# charger.net
KiCad netlist of a schematic drawn in EAGLE
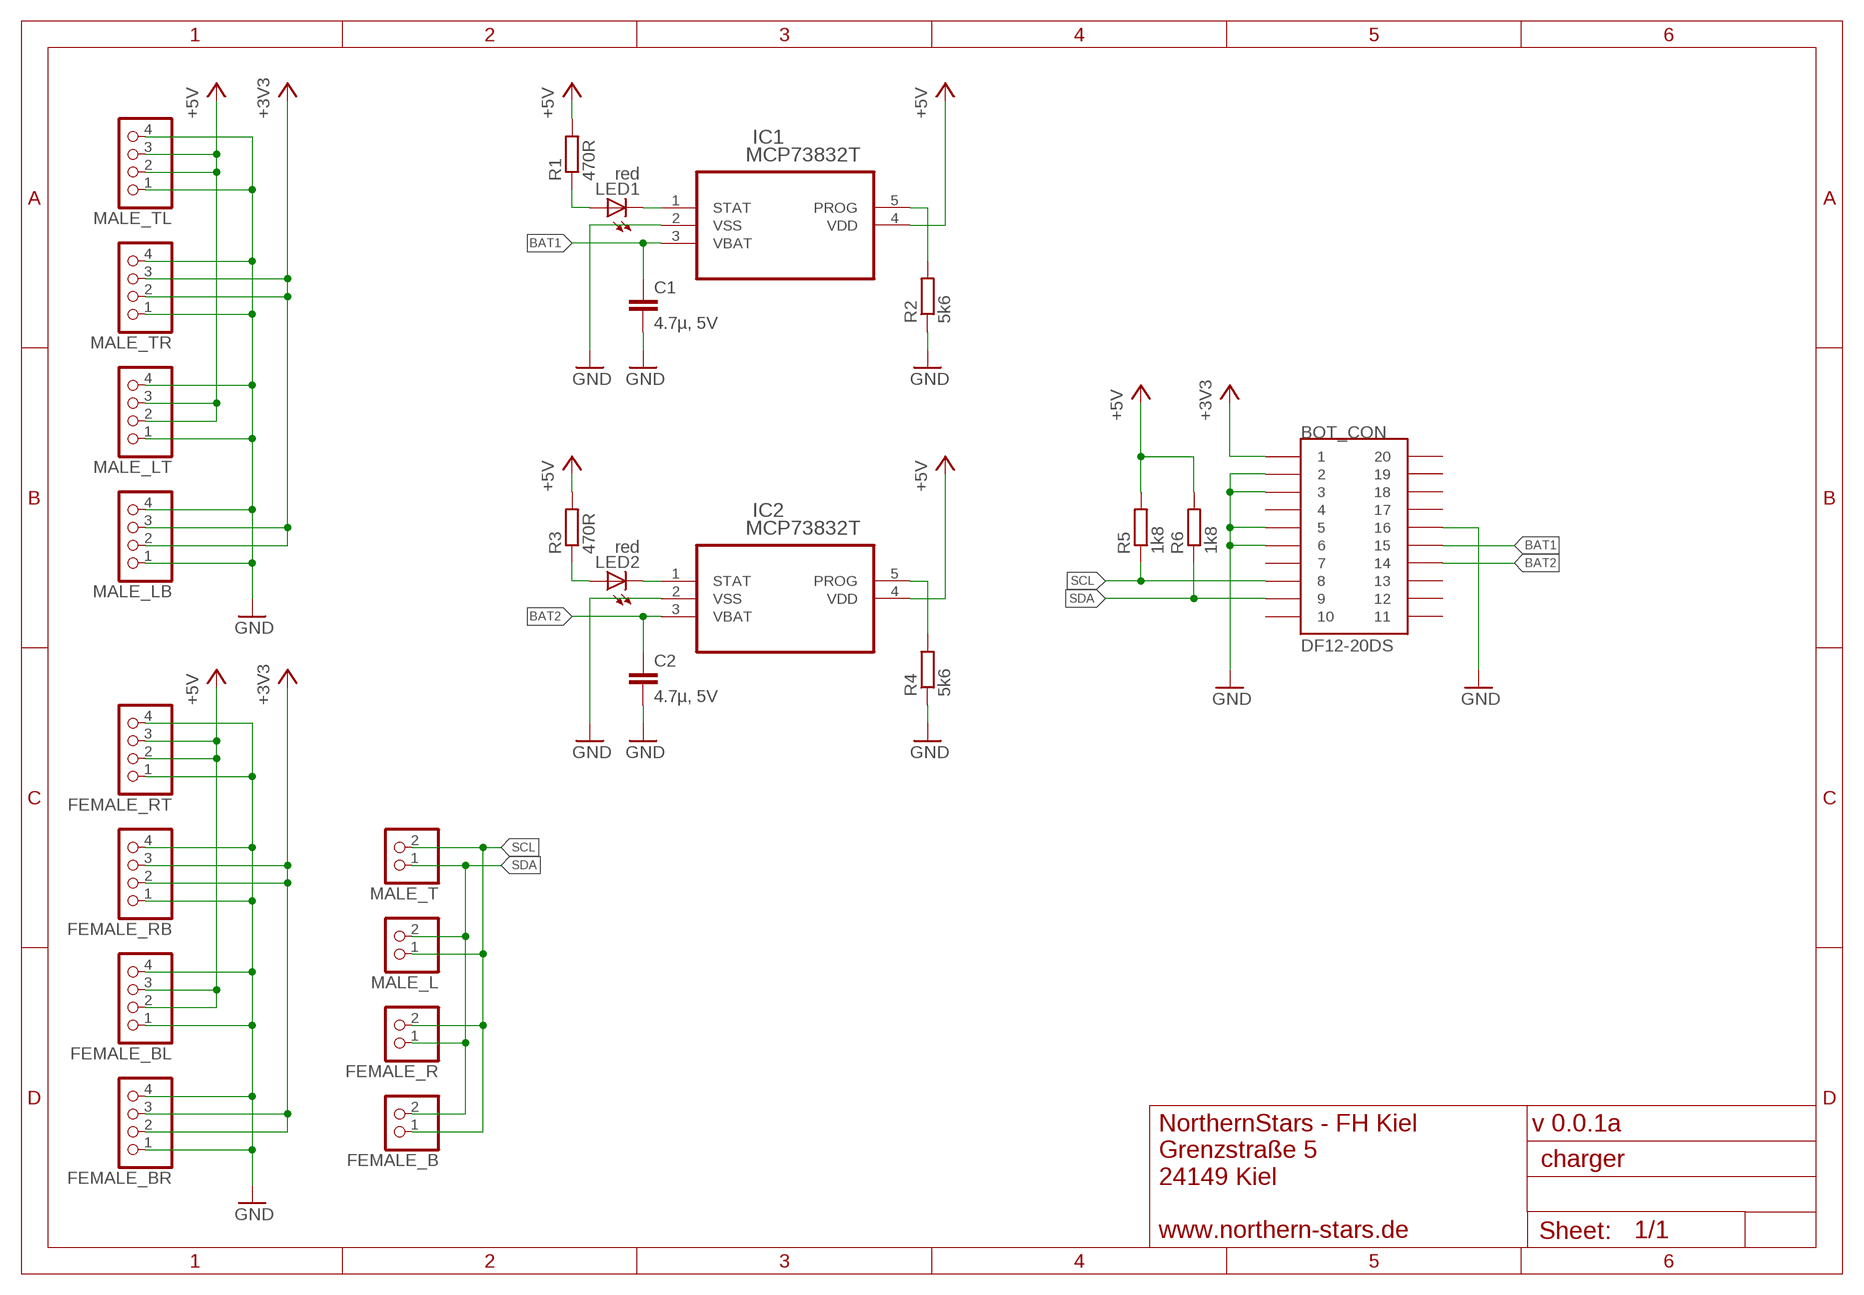
[diagram p0: schematic, sheet 1]

(export (version "E")
  (design (tool "Eeschema 10.0.6"))
  (components
    (comp (ref "BOT_CON")
      (value "DF12-20DS")
      (footprint "eagle-import:DF12-20DS")
      (libsource (lib "eagle-import") (part "DF12-20DS"))
    )
    (comp (ref "C1")
      (value "4.7µ, 5V")
      (footprint "eagle-import:C1206")
      (libsource (lib "eagle-import") (part "C-EUC1206"))
    )
    (comp (ref "C2")
      (value "4.7µ, 5V")
      (footprint "eagle-import:C1206")
      (libsource (lib "eagle-import") (part "C-EUC1206"))
    )
    (comp (ref "FEMALE_B")
      (value "PINHD-1X02_2.54-90°")
      (footprint "eagle-import:1X02_90")
      (libsource (lib "eagle-import") (part "PINHD-1X02_2.54-90°"))
    )
    (comp (ref "FEMALE_BL")
      (value "PINHD-1X04_2.54-90°")
      (footprint "eagle-import:1X04_90")
      (libsource (lib "eagle-import") (part "PINHD-1X04_2.54-90°"))
    )
    (comp (ref "FEMALE_BR")
      (value "PINHD-1X04_2.54-90°")
      (footprint "eagle-import:1X04_90")
      (libsource (lib "eagle-import") (part "PINHD-1X04_2.54-90°"))
    )
    (comp (ref "FEMALE_R")
      (value "PINHD-1X02_2.54-90°")
      (footprint "eagle-import:1X02_90")
      (libsource (lib "eagle-import") (part "PINHD-1X02_2.54-90°"))
    )
    (comp (ref "FEMALE_RB")
      (value "PINHD-1X04_2.54-90°")
      (footprint "eagle-import:1X04_90")
      (libsource (lib "eagle-import") (part "PINHD-1X04_2.54-90°"))
    )
    (comp (ref "FEMALE_RT")
      (value "PINHD-1X04_2.54-90°")
      (footprint "eagle-import:1X04_90")
      (libsource (lib "eagle-import") (part "PINHD-1X04_2.54-90°"))
    )
    (comp (ref "IC1")
      (value "MCP73832T")
      (footprint "eagle-import:SOT95P300X145-5N")
      (fields (field (name "MPN") "MCP73832T-2DCI/OT"))
      (libsource (lib "eagle-import") (part "MCP73832T-2DCI/OT"))
    )
    (comp (ref "IC2")
      (value "MCP73832T")
      (footprint "eagle-import:SOT95P300X145-5N")
      (fields (field (name "MPN") "MCP73832T-2DCI/OT"))
      (libsource (lib "eagle-import") (part "MCP73832T-2DCI/OT"))
    )
    (comp (ref "LED1")
      (value "red")
      (footprint "eagle-import:CHIPLED_1206")
      (libsource (lib "eagle-import") (part "LEDCHIPLED_1206"))
    )
    (comp (ref "LED2")
      (value "red")
      (footprint "eagle-import:CHIPLED_1206")
      (libsource (lib "eagle-import") (part "LEDCHIPLED_1206"))
    )
    (comp (ref "MALE_L")
      (value "PINHD-1X02_2.54-90°")
      (footprint "eagle-import:1X02_90")
      (libsource (lib "eagle-import") (part "PINHD-1X02_2.54-90°"))
    )
    (comp (ref "MALE_LB")
      (value "PINHD-1X04_2.54-90°")
      (footprint "eagle-import:1X04_90")
      (libsource (lib "eagle-import") (part "PINHD-1X04_2.54-90°"))
    )
    (comp (ref "MALE_LT")
      (value "PINHD-1X04_2.54-90°")
      (footprint "eagle-import:1X04_90")
      (libsource (lib "eagle-import") (part "PINHD-1X04_2.54-90°"))
    )
    (comp (ref "MALE_T")
      (value "PINHD-1X02_2.54-90°")
      (footprint "eagle-import:1X02_90")
      (libsource (lib "eagle-import") (part "PINHD-1X02_2.54-90°"))
    )
    (comp (ref "MALE_TL")
      (value "PINHD-1X04_2.54-90°")
      (footprint "eagle-import:1X04_90")
      (libsource (lib "eagle-import") (part "PINHD-1X04_2.54-90°"))
    )
    (comp (ref "MALE_TR")
      (value "PINHD-1X04_2.54-90°")
      (footprint "eagle-import:1X04_90")
      (libsource (lib "eagle-import") (part "PINHD-1X04_2.54-90°"))
    )
    (comp (ref "R1")
      (value "470R")
      (footprint "eagle-import:R1206")
      (libsource (lib "eagle-import") (part "R-EU_R1206"))
    )
    (comp (ref "R2")
      (value "5k6")
      (footprint "eagle-import:R1206")
      (libsource (lib "eagle-import") (part "R-EU_R1206"))
    )
    (comp (ref "R3")
      (value "470R")
      (footprint "eagle-import:R1206")
      (libsource (lib "eagle-import") (part "R-EU_R1206"))
    )
    (comp (ref "R4")
      (value "5k6")
      (footprint "eagle-import:R1206")
      (libsource (lib "eagle-import") (part "R-EU_R1206"))
    )
    (comp (ref "R5")
      (value "1k8")
      (footprint "eagle-import:R1206")
      (libsource (lib "eagle-import") (part "R-EU_R1206"))
    )
    (comp (ref "R6")
      (value "1k8")
      (footprint "eagle-import:R1206")
      (libsource (lib "eagle-import") (part "R-EU_R1206"))
    )
  )
  (nets
    (net (code "1") (name "+3V3") (class "Default")
      (node (ref "BOT_CON") (pin "1") (pinfunction "1_1") (pintype "bidirectional"))
      (node (ref "FEMALE_BR") (pin "2") (pinfunction "2_2") (pintype "passive"))
      (node (ref "FEMALE_BR") (pin "3") (pinfunction "3_3") (pintype "passive"))
      (node (ref "FEMALE_RB") (pin "2") (pinfunction "2_2") (pintype "passive"))
      (node (ref "FEMALE_RB") (pin "3") (pinfunction "3_3") (pintype "passive"))
      (node (ref "MALE_LB") (pin "2") (pinfunction "2_2") (pintype "passive"))
      (node (ref "MALE_LB") (pin "3") (pinfunction "3_3") (pintype "passive"))
      (node (ref "MALE_TR") (pin "2") (pinfunction "2_2") (pintype "passive"))
      (node (ref "MALE_TR") (pin "3") (pinfunction "3_3") (pintype "passive"))
    )
    (net (code "2") (name "+5V") (class "Default")
      (node (ref "FEMALE_BL") (pin "2") (pinfunction "2_2") (pintype "passive"))
      (node (ref "FEMALE_BL") (pin "3") (pinfunction "3_3") (pintype "passive"))
      (node (ref "FEMALE_RT") (pin "2") (pinfunction "2_2") (pintype "passive"))
      (node (ref "FEMALE_RT") (pin "3") (pinfunction "3_3") (pintype "passive"))
      (node (ref "IC1") (pin "4") (pinfunction "VDD_4") (pintype "power_in"))
      (node (ref "IC2") (pin "4") (pinfunction "VDD_4") (pintype "power_in"))
      (node (ref "MALE_LT") (pin "2") (pinfunction "2_2") (pintype "passive"))
      (node (ref "MALE_LT") (pin "3") (pinfunction "3_3") (pintype "passive"))
      (node (ref "MALE_TL") (pin "2") (pinfunction "2_2") (pintype "passive"))
      (node (ref "MALE_TL") (pin "3") (pinfunction "3_3") (pintype "passive"))
      (node (ref "R1") (pin "2") (pinfunction "2_2") (pintype "passive"))
      (node (ref "R3") (pin "2") (pinfunction "2_2") (pintype "passive"))
      (node (ref "R5") (pin "2") (pinfunction "2_2") (pintype "passive"))
      (node (ref "R6") (pin "2") (pinfunction "2_2") (pintype "passive"))
    )
    (net (code "3") (name "BAT1") (class "Default")
      (node (ref "BOT_CON") (pin "15") (pinfunction "15_15") (pintype "bidirectional"))
      (node (ref "C1") (pin "1") (pinfunction "1_1") (pintype "passive"))
      (node (ref "IC1") (pin "3") (pinfunction "VBAT_3") (pintype "input"))
    )
    (net (code "4") (name "BAT2") (class "Default")
      (node (ref "BOT_CON") (pin "14") (pinfunction "14_14") (pintype "bidirectional"))
      (node (ref "C2") (pin "1") (pinfunction "1_1") (pintype "passive"))
      (node (ref "IC2") (pin "3") (pinfunction "VBAT_3") (pintype "input"))
    )
    (net (code "5") (name "GND") (class "Default")
      (node (ref "BOT_CON") (pin "16") (pinfunction "16_16") (pintype "bidirectional"))
      (node (ref "BOT_CON") (pin "2") (pinfunction "2_2") (pintype "bidirectional"))
      (node (ref "BOT_CON") (pin "3") (pinfunction "3_3") (pintype "bidirectional"))
      (node (ref "BOT_CON") (pin "5") (pinfunction "5_5") (pintype "bidirectional"))
      (node (ref "BOT_CON") (pin "6") (pinfunction "6_6") (pintype "bidirectional"))
      (node (ref "C1") (pin "2") (pinfunction "2_2") (pintype "passive"))
      (node (ref "C2") (pin "2") (pinfunction "2_2") (pintype "passive"))
      (node (ref "FEMALE_BL") (pin "1") (pinfunction "1_1") (pintype "passive"))
      (node (ref "FEMALE_BL") (pin "4") (pinfunction "4_4") (pintype "passive"))
      (node (ref "FEMALE_BR") (pin "1") (pinfunction "1_1") (pintype "passive"))
      (node (ref "FEMALE_BR") (pin "4") (pinfunction "4_4") (pintype "passive"))
      (node (ref "FEMALE_RB") (pin "1") (pinfunction "1_1") (pintype "passive"))
      (node (ref "FEMALE_RB") (pin "4") (pinfunction "4_4") (pintype "passive"))
      (node (ref "FEMALE_RT") (pin "1") (pinfunction "1_1") (pintype "passive"))
      (node (ref "FEMALE_RT") (pin "4") (pinfunction "4_4") (pintype "passive"))
      (node (ref "IC1") (pin "2") (pinfunction "VSS_2") (pintype "passive"))
      (node (ref "IC2") (pin "2") (pinfunction "VSS_2") (pintype "passive"))
      (node (ref "MALE_LB") (pin "1") (pinfunction "1_1") (pintype "passive"))
      (node (ref "MALE_LB") (pin "4") (pinfunction "4_4") (pintype "passive"))
      (node (ref "MALE_LT") (pin "1") (pinfunction "1_1") (pintype "passive"))
      (node (ref "MALE_LT") (pin "4") (pinfunction "4_4") (pintype "passive"))
      (node (ref "MALE_TL") (pin "1") (pinfunction "1_1") (pintype "passive"))
      (node (ref "MALE_TL") (pin "4") (pinfunction "4_4") (pintype "passive"))
      (node (ref "MALE_TR") (pin "1") (pinfunction "1_1") (pintype "passive"))
      (node (ref "MALE_TR") (pin "4") (pinfunction "4_4") (pintype "passive"))
      (node (ref "R2") (pin "1") (pinfunction "1_1") (pintype "passive"))
      (node (ref "R4") (pin "1") (pinfunction "1_1") (pintype "passive"))
    )
    (net (code "6") (name "Net-(IC1-PROG)") (class "Default")
      (node (ref "IC1") (pin "5") (pinfunction "PROG_5") (pintype "input"))
      (node (ref "R2") (pin "2") (pinfunction "2_2") (pintype "passive"))
    )
    (net (code "7") (name "Net-(IC1-STAT)") (class "Default")
      (node (ref "IC1") (pin "1") (pinfunction "STAT_1") (pintype "input"))
      (node (ref "LED1") (pin "C") (pinfunction "C_C") (pintype "passive"))
    )
    (net (code "8") (name "Net-(IC2-PROG)") (class "Default")
      (node (ref "IC2") (pin "5") (pinfunction "PROG_5") (pintype "input"))
      (node (ref "R4") (pin "2") (pinfunction "2_2") (pintype "passive"))
    )
    (net (code "9") (name "Net-(IC2-STAT)") (class "Default")
      (node (ref "IC2") (pin "1") (pinfunction "STAT_1") (pintype "input"))
      (node (ref "LED2") (pin "C") (pinfunction "C_C") (pintype "passive"))
    )
    (net (code "10") (name "Net-(LED1-PadA)") (class "Default")
      (node (ref "LED1") (pin "A") (pinfunction "A_A") (pintype "passive"))
      (node (ref "R1") (pin "1") (pinfunction "1_1") (pintype "passive"))
    )
    (net (code "11") (name "Net-(LED2-PadA)") (class "Default")
      (node (ref "LED2") (pin "A") (pinfunction "A_A") (pintype "passive"))
      (node (ref "R3") (pin "1") (pinfunction "1_1") (pintype "passive"))
    )
    (net (code "12") (name "SCL") (class "Default")
      (node (ref "BOT_CON") (pin "8") (pinfunction "8_8") (pintype "bidirectional"))
      (node (ref "FEMALE_B") (pin "1") (pinfunction "1_1") (pintype "passive"))
      (node (ref "FEMALE_R") (pin "2") (pinfunction "2_2") (pintype "passive"))
      (node (ref "MALE_L") (pin "1") (pinfunction "1_1") (pintype "passive"))
      (node (ref "MALE_T") (pin "2") (pinfunction "2_2") (pintype "passive"))
      (node (ref "R5") (pin "1") (pinfunction "1_1") (pintype "passive"))
    )
    (net (code "13") (name "SDA") (class "Default")
      (node (ref "BOT_CON") (pin "9") (pinfunction "9_9") (pintype "bidirectional"))
      (node (ref "FEMALE_B") (pin "2") (pinfunction "2_2") (pintype "passive"))
      (node (ref "FEMALE_R") (pin "1") (pinfunction "1_1") (pintype "passive"))
      (node (ref "MALE_L") (pin "2") (pinfunction "2_2") (pintype "passive"))
      (node (ref "MALE_T") (pin "1") (pinfunction "1_1") (pintype "passive"))
      (node (ref "R6") (pin "1") (pinfunction "1_1") (pintype "passive"))
    )
    (net (code "14") (name "unconnected-(BOT_CON-Pad4)") (class "Default")
      (node (ref "BOT_CON") (pin "4") (pinfunction "4_4") (pintype "bidirectional"))
    )
    (net (code "15") (name "unconnected-(BOT_CON-Pad7)") (class "Default")
      (node (ref "BOT_CON") (pin "7") (pinfunction "7_7") (pintype "bidirectional"))
    )
    (net (code "16") (name "unconnected-(BOT_CON-Pad10)") (class "Default")
      (node (ref "BOT_CON") (pin "10") (pinfunction "10_10") (pintype "bidirectional"))
    )
    (net (code "17") (name "unconnected-(BOT_CON-Pad11)") (class "Default")
      (node (ref "BOT_CON") (pin "11") (pinfunction "11_11") (pintype "bidirectional"))
    )
    (net (code "18") (name "unconnected-(BOT_CON-Pad12)") (class "Default")
      (node (ref "BOT_CON") (pin "12") (pinfunction "12_12") (pintype "bidirectional"))
    )
    (net (code "19") (name "unconnected-(BOT_CON-Pad13)") (class "Default")
      (node (ref "BOT_CON") (pin "13") (pinfunction "13_13") (pintype "bidirectional"))
    )
    (net (code "20") (name "unconnected-(BOT_CON-Pad17)") (class "Default")
      (node (ref "BOT_CON") (pin "17") (pinfunction "17_17") (pintype "bidirectional"))
    )
    (net (code "21") (name "unconnected-(BOT_CON-Pad18)") (class "Default")
      (node (ref "BOT_CON") (pin "18") (pinfunction "18_18") (pintype "bidirectional"))
    )
    (net (code "22") (name "unconnected-(BOT_CON-Pad19)") (class "Default")
      (node (ref "BOT_CON") (pin "19") (pinfunction "19_19") (pintype "bidirectional"))
    )
    (net (code "23") (name "unconnected-(BOT_CON-Pad20)") (class "Default")
      (node (ref "BOT_CON") (pin "20") (pinfunction "20_20") (pintype "bidirectional"))
    )
  )
)
